# ReuseBlock_PacheckPhaseDriver_2024-09-21.net
KiCad netlist of a schematic drawn in EasyEDA Pro
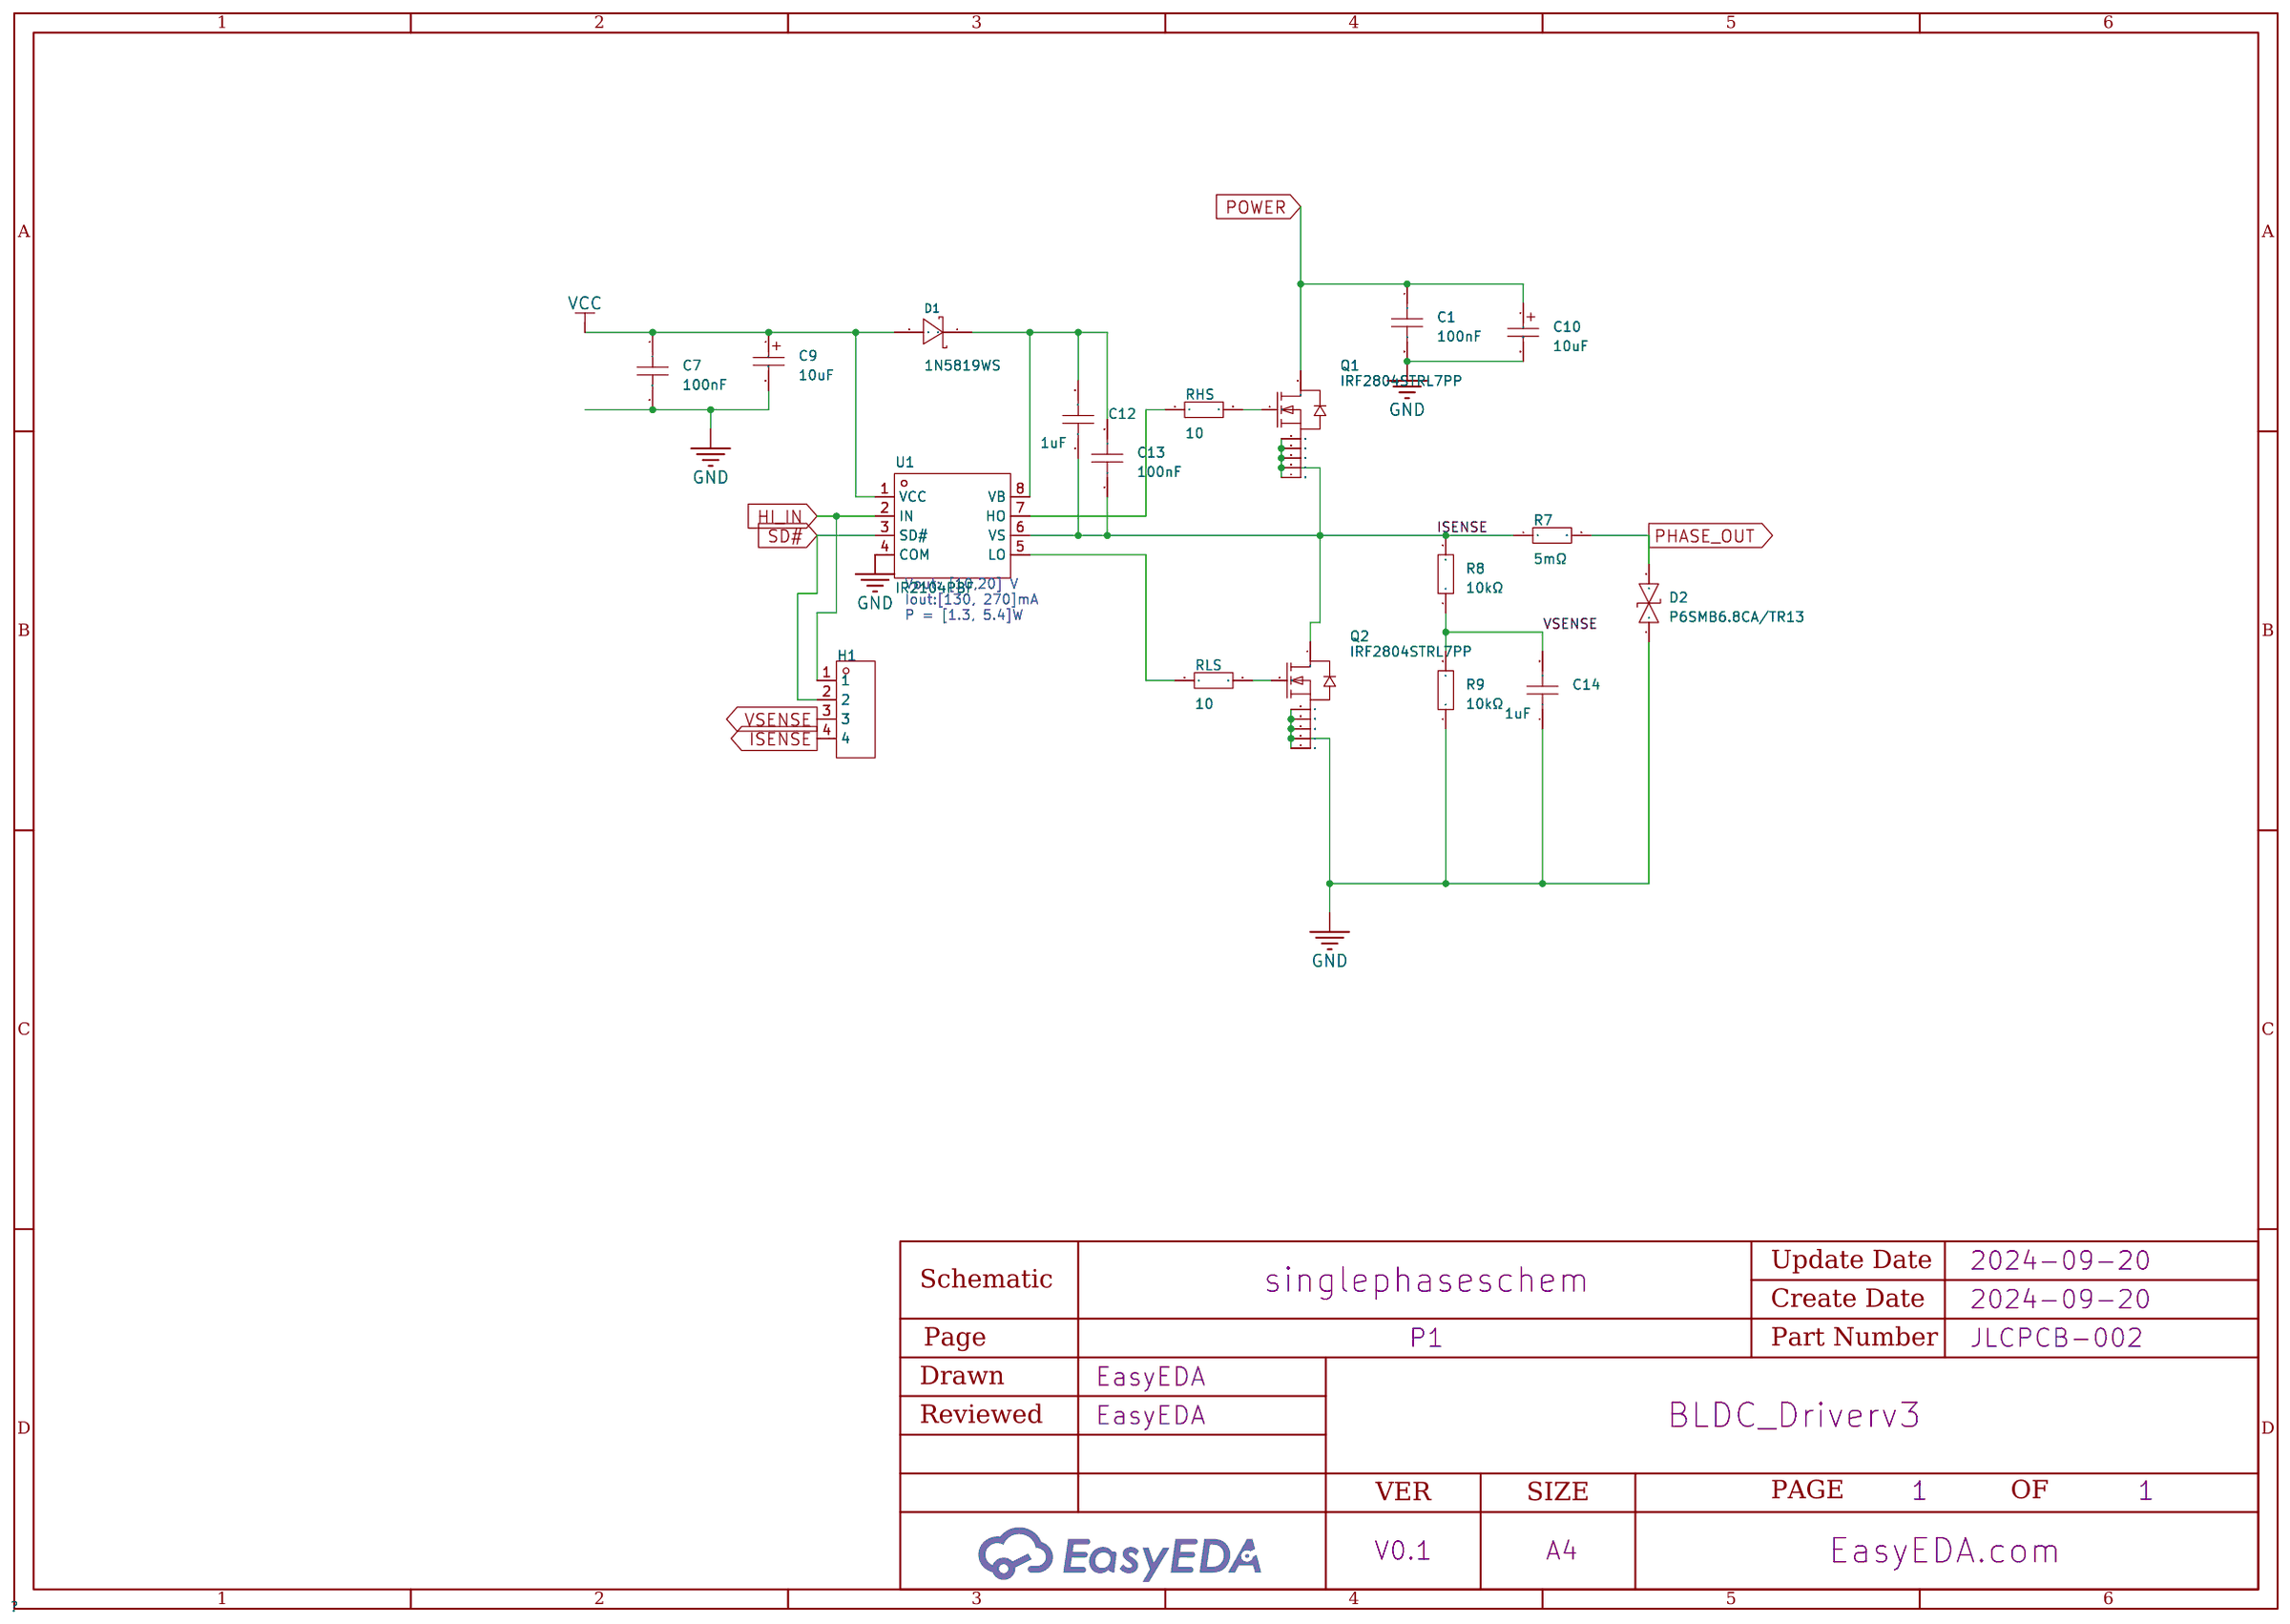
[diagram p0: schematic sheet]

(export (version "E")
  (design (tool "Eeschema 10.0.6"))
  (components
    (comp (ref "C1")
      (value "100nF")
      (footprint "easyedapro:C0603")
      (libsource (lib "easyedapro") (part "CAP"))
    )
    (comp (ref "C7")
      (value "100nF")
      (footprint "easyedapro:C0603")
      (libsource (lib "easyedapro") (part "CAP"))
    )
    (comp (ref "C9")
      (value "10uF")
      (footprint "easyedapro:CAP-SMD_BD5.0-L5.3-W5.3-LS6.3-FD")
      (libsource (lib "easyedapro") (part "C_Ele_SMD"))
    )
    (comp (ref "C10")
      (value "10uF")
      (footprint "easyedapro:CAP-SMD_BD5.0-L5.3-W5.3-LS6.3-FD")
      (libsource (lib "easyedapro") (part "C_Ele_SMD"))
    )
    (comp (ref "C12")
      (value "1uF")
      (footprint "easyedapro:CAP-TH_L7.2-W2.5-P5.00-D0.6")
      (fields (field (name "Manufacturer Part") "SMEC334J100M2") (field (name "Manufacturer") "CHAMPION(全鹏)"))
      (libsource (lib "easyedapro") (part "SMEC334J100M2"))
    )
    (comp (ref "C13")
      (value "100nF")
      (footprint "easyedapro:C0603")
      (libsource (lib "easyedapro") (part "CAP"))
    )
    (comp (ref "C14")
      (value "1uF")
      (footprint "easyedapro:CAP-TH_L7.2-W2.5-P5.00-D0.6")
      (fields (field (name "Manufacturer Part") "SMEC334J100M2") (field (name "Manufacturer") "CHAMPION(全鹏)"))
      (libsource (lib "easyedapro") (part "SMEC334J100M2"))
    )
    (comp (ref "D1")
      (value "1N5819WS")
      (footprint "easyedapro:SOD-323_L1.8-W1.3-LS2.5-RD")
      (description "Forward Voltage (Vf@If):600mV@1A Reverse Voltage (Vr):40V Average Rectified Current (Io):1A")
      (fields (field (name "Manufacturer") "Hottech(合科泰)"))
      (libsource (lib "easyedapro") (part "1N5819WS"))
    )
    (comp (ref "D2")
      (value "P6SMB6.8CA/TR13")
      (footprint "easyedapro:SMB_L4.6-W3.6-LS5.3-BI")
      (fields (field (name "Manufacturer") "Brightking(君耀电子)"))
      (libsource (lib "easyedapro") (part "P6SMB6.8CA-C78395"))
    )
    (comp (ref "H1")
      (value "~")
      (footprint "easyedapro:HDR-TH_4P-P2.54-V-M")
      (libsource (lib "easyedapro") (part "PZ254V-11-04P"))
    )
    (comp (ref "Q1")
      (value "IRF2804STRL7PP")
      (footprint "easyedapro:D2PAK-7_L10.6-W9.6-P1.27-LS15.9-BR")
      (fields (field (name "Manufacturer") "Infineon(英飞凌)"))
      (libsource (lib "easyedapro") (part "IRF2804STRL7PP"))
    )
    (comp (ref "Q2")
      (value "IRF2804STRL7PP")
      (footprint "easyedapro:D2PAK-7_L10.6-W9.6-P1.27-LS15.9-BR")
      (fields (field (name "Manufacturer") "Infineon(英飞凌)"))
      (libsource (lib "easyedapro") (part "IRF2804STRL7PP"))
    )
    (comp (ref "R7")
      (value "5mΩ")
      (footprint "easyedapro:R2512")
      (fields
        (field (name "Manufacturer Part") "PA2512FKF7W0R005E")
        (field (name "Manufacturer") "YAGEO(国巨)")
      )
      (libsource (lib "easyedapro") (part "PA2512FKF7W0R005L"))
    )
    (comp (ref "R8")
      (value "10kΩ")
      (footprint "easyedapro:R1210")
      (libsource (lib "easyedapro") (part "Res"))
    )
    (comp (ref "R9")
      (value "10kΩ")
      (footprint "easyedapro:R1210")
      (libsource (lib "easyedapro") (part "Res"))
    )
    (comp (ref "RHS") (value "10") (footprint "easyedapro:R1210") (libsource (lib "easyedapro") (part "Res")))
    (comp (ref "RLS") (value "10") (footprint "easyedapro:R1210") (libsource (lib "easyedapro") (part "Res")))
    (comp (ref "U1")
      (value "IR2104PBF")
      (footprint "easyedapro:DIP-8_L9.9-W6.6-P2.54-LS7.62-BL")
      (fields (field (name "Manufacturer") "Infineon(英飞凌)"))
      (libsource (lib "easyedapro") (part "IR2104PBF"))
    )
  )
  (nets
    (net (code "1") (name "GND") (class "Default")
      (node (ref "C1") (pin "2") (pinfunction "2_2") (pintype "input"))
      (node (ref "C10") (pin "2") (pinfunction "2_2") (pintype "input"))
      (node (ref "C14") (pin "1") (pinfunction "1_1") (pintype "input"))
      (node (ref "C7") (pin "2") (pinfunction "2_2") (pintype "input"))
      (node (ref "C9") (pin "2") (pinfunction "2_2") (pintype "input"))
      (node (ref "D2") (pin "1") (pinfunction "1_1") (pintype "unspecified"))
      (node (ref "Q2") (pin "2") (pinfunction "S_2") (pintype "unspecified"))
      (node (ref "Q2") (pin "3") (pinfunction "S_3") (pintype "unspecified"))
      (node (ref "Q2") (pin "5") (pinfunction "S_5") (pintype "unspecified"))
      (node (ref "Q2") (pin "6") (pinfunction "S_6") (pintype "unspecified"))
      (node (ref "Q2") (pin "7") (pinfunction "S_7") (pintype "unspecified"))
      (node (ref "R9") (pin "1") (pinfunction "1_1") (pintype "input"))
      (node (ref "U1") (pin "4") (pinfunction "COM_4") (pintype "unspecified"))
    )
    (net (code "2") (name "HI_IN") (class "Default")
      (node (ref "H1") (pin "1") (pinfunction "1_1") (pintype "unspecified"))
      (node (ref "U1") (pin "2") (pinfunction "IN_2") (pintype "unspecified"))
    )
    (net (code "3") (name "ISENSE") (class "Default")
      (node (ref "C12") (pin "1") (pinfunction "1_1") (pintype "input"))
      (node (ref "C13") (pin "2") (pinfunction "2_2") (pintype "input"))
      (node (ref "H1") (pin "4") (pinfunction "4_4") (pintype "unspecified"))
      (node (ref "Q1") (pin "2") (pinfunction "S_2") (pintype "unspecified"))
      (node (ref "Q1") (pin "3") (pinfunction "S_3") (pintype "unspecified"))
      (node (ref "Q1") (pin "5") (pinfunction "S_5") (pintype "unspecified"))
      (node (ref "Q1") (pin "6") (pinfunction "S_6") (pintype "unspecified"))
      (node (ref "Q1") (pin "7") (pinfunction "S_7") (pintype "unspecified"))
      (node (ref "Q2") (pin "4") (pinfunction "D_4") (pintype "unspecified"))
      (node (ref "R7") (pin "1") (pinfunction "1_1") (pintype "unspecified"))
      (node (ref "R8") (pin "2") (pinfunction "2_2") (pintype "input"))
      (node (ref "U1") (pin "6") (pinfunction "VS_6") (pintype "unspecified"))
    )
    (net (code "4") (name "Net-(D1-K)") (class "Default")
      (node (ref "C12") (pin "2") (pinfunction "2_2") (pintype "input"))
      (node (ref "C13") (pin "1") (pinfunction "1_1") (pintype "input"))
      (node (ref "D1") (pin "1") (pinfunction "K_1") (pintype "input"))
      (node (ref "U1") (pin "8") (pinfunction "VB_8") (pintype "unspecified"))
    )
    (net (code "5") (name "Net-(Q1-G)") (class "Default")
      (node (ref "Q1") (pin "1") (pinfunction "G_1") (pintype "unspecified"))
      (node (ref "RHS") (pin "2") (pinfunction "2_2") (pintype "input"))
    )
    (net (code "6") (name "Net-(Q2-G)") (class "Default")
      (node (ref "Q2") (pin "1") (pinfunction "G_1") (pintype "unspecified"))
      (node (ref "RLS") (pin "2") (pinfunction "2_2") (pintype "input"))
    )
    (net (code "7") (name "Net-(U1-HO)") (class "Default")
      (node (ref "RHS") (pin "1") (pinfunction "1_1") (pintype "input"))
      (node (ref "U1") (pin "7") (pinfunction "HO_7") (pintype "unspecified"))
    )
    (net (code "8") (name "Net-(U1-LO)") (class "Default")
      (node (ref "RLS") (pin "1") (pinfunction "1_1") (pintype "input"))
      (node (ref "U1") (pin "5") (pinfunction "LO_5") (pintype "unspecified"))
    )
    (net (code "9") (name "PHASE_OUT") (class "Default")
      (node (ref "D2") (pin "2") (pinfunction "2_2") (pintype "unspecified"))
      (node (ref "R7") (pin "2") (pinfunction "2_2") (pintype "unspecified"))
    )
    (net (code "10") (name "POWER") (class "Default")
      (node (ref "C1") (pin "1") (pinfunction "1_1") (pintype "input"))
      (node (ref "C10") (pin "1") (pinfunction "1_1") (pintype "input"))
      (node (ref "Q1") (pin "4") (pinfunction "D_4") (pintype "unspecified"))
    )
    (net (code "11") (name "SD#") (class "Default")
      (node (ref "H1") (pin "2") (pinfunction "2_2") (pintype "unspecified"))
      (node (ref "U1") (pin "3") (pinfunction "SD#_3") (pintype "unspecified"))
    )
    (net (code "12") (name "VCC") (class "Default")
      (node (ref "C7") (pin "1") (pinfunction "1_1") (pintype "input"))
      (node (ref "C9") (pin "1") (pinfunction "1_1") (pintype "input"))
      (node (ref "D1") (pin "2") (pinfunction "A_2") (pintype "input"))
      (node (ref "U1") (pin "1") (pinfunction "VCC_1") (pintype "unspecified"))
    )
    (net (code "13") (name "VSENSE") (class "Default")
      (node (ref "C14") (pin "2") (pinfunction "2_2") (pintype "input"))
      (node (ref "H1") (pin "3") (pinfunction "3_3") (pintype "unspecified"))
      (node (ref "R8") (pin "1") (pinfunction "1_1") (pintype "input"))
      (node (ref "R9") (pin "2") (pinfunction "2_2") (pintype "input"))
    )
  )
)
